# Sheet2.net
KiCad netlist of a schematic drawn in Altium Designer
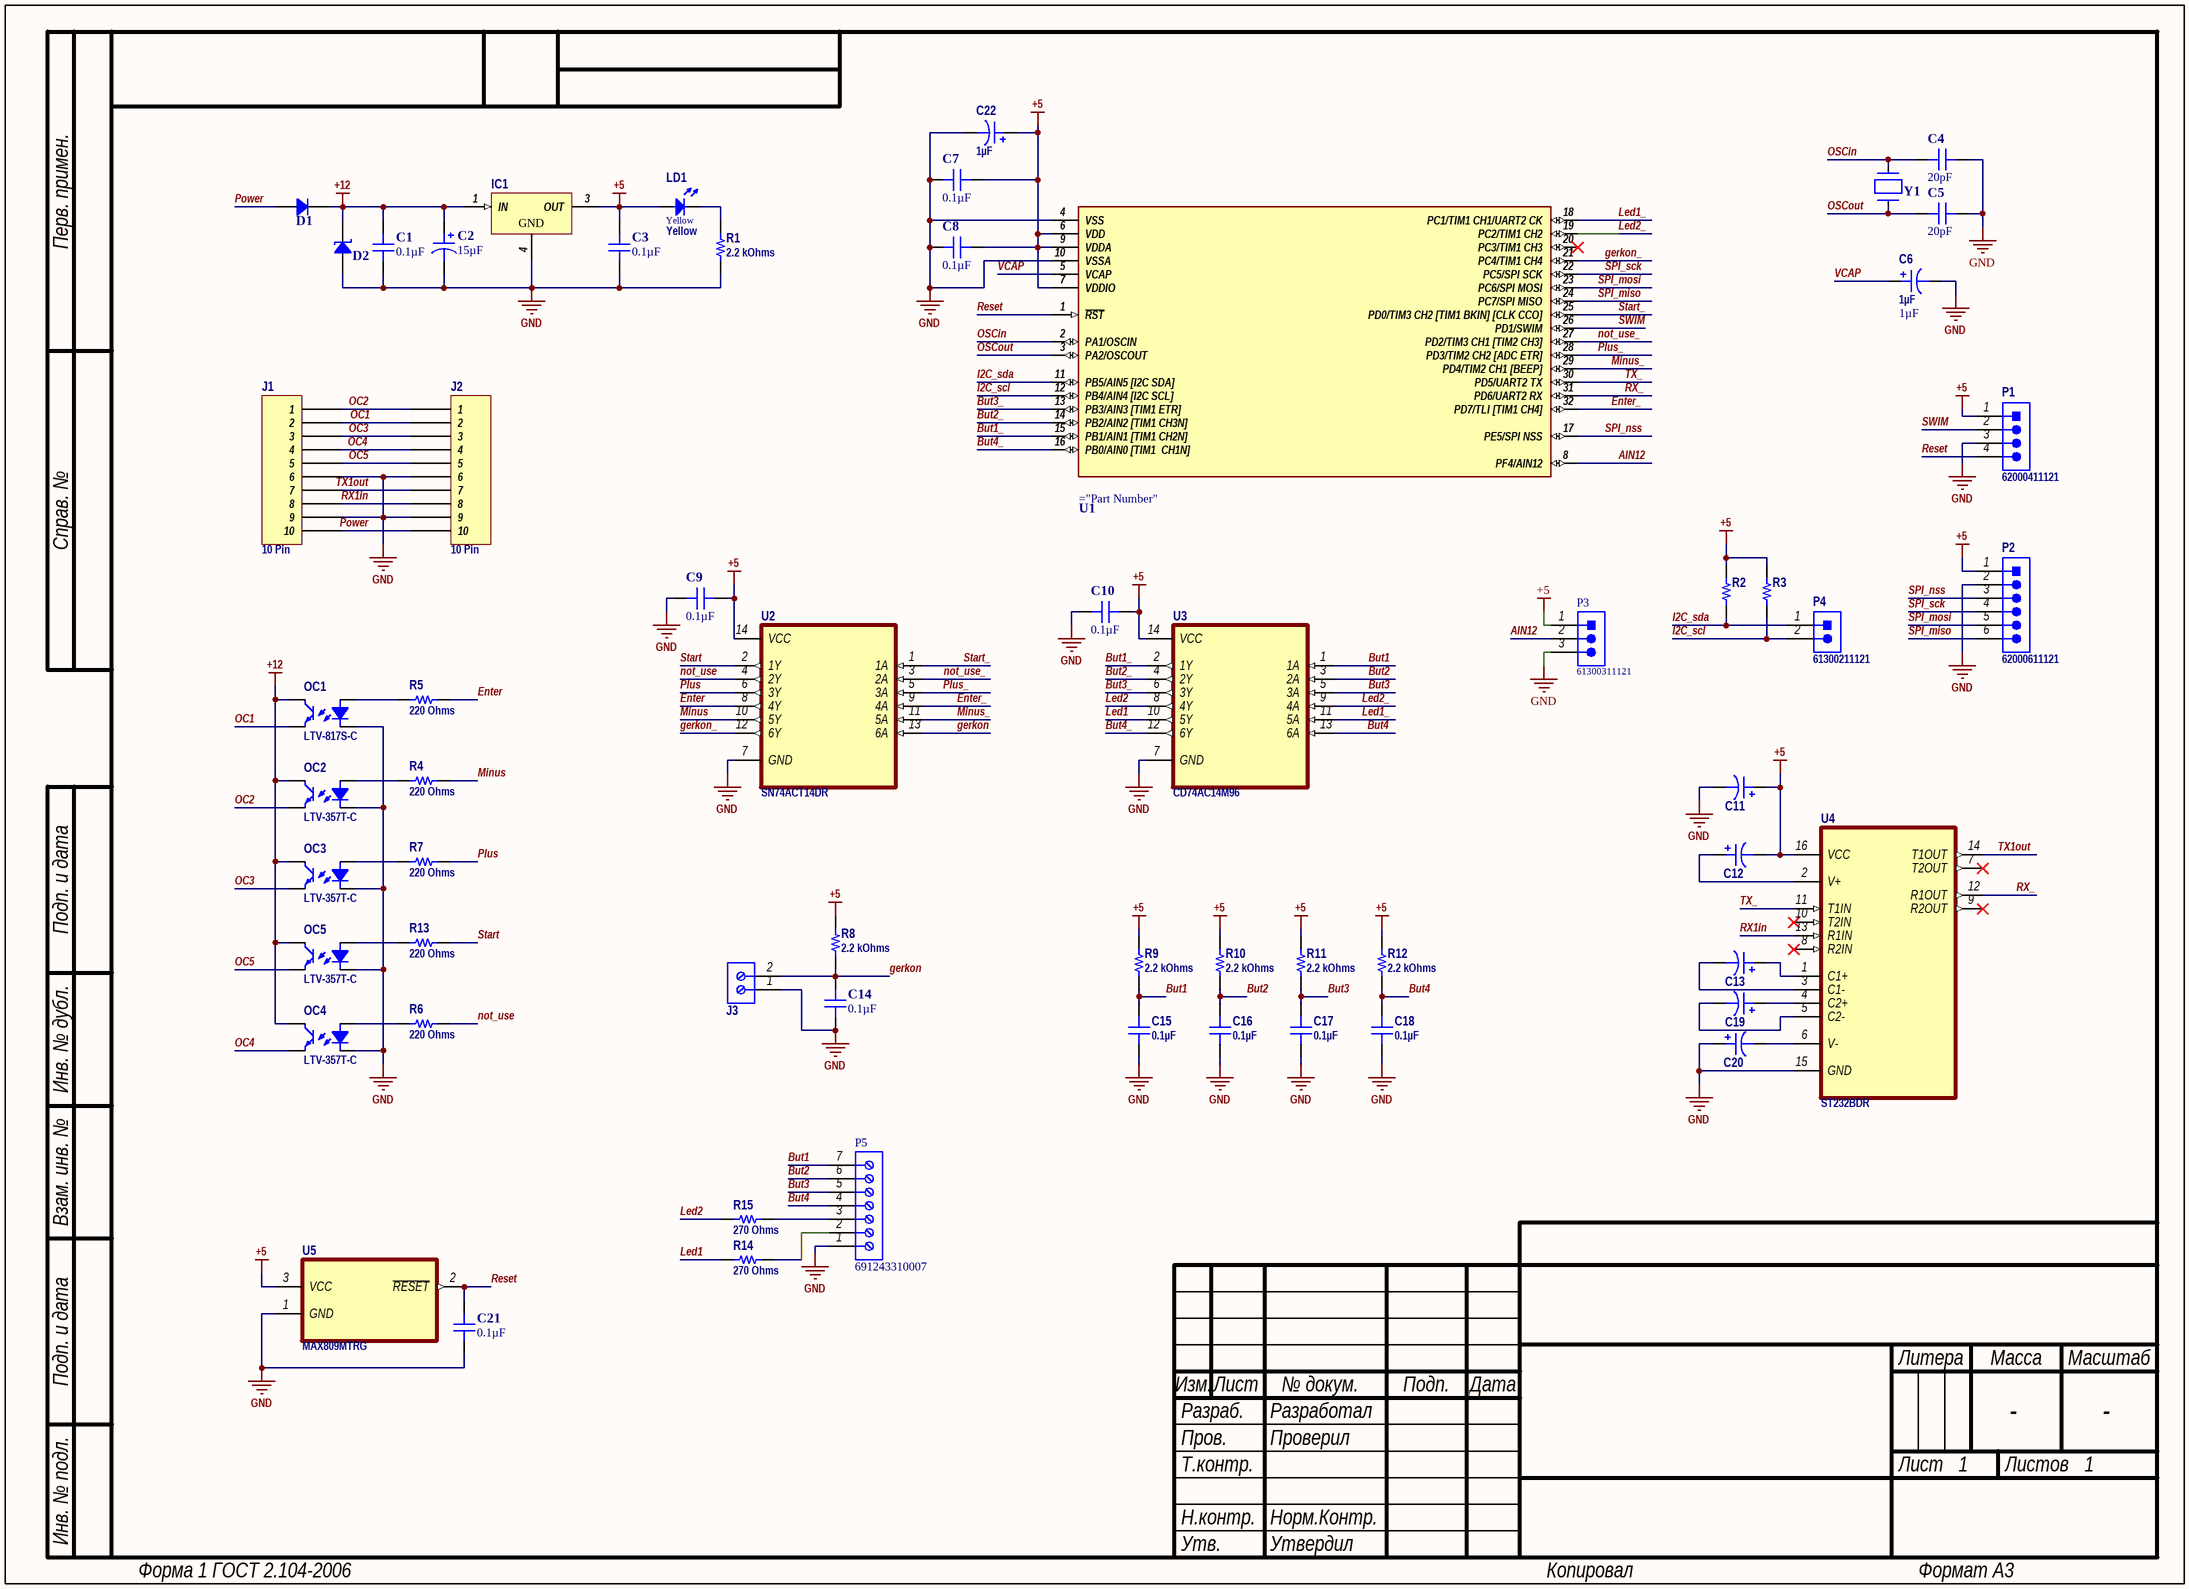
[diagram p0: Sheet2.SchDoc]

(export (version "E")
  (design (tool "Eeschema 10.0.6"))
  (components
    (comp (ref "C1")
      (value "0.1µF")
      (footprint "CAP 0603_1608")
      (description "CAP CER 0.1UF 50V X5R 0603")
      (fields (field (name "PART NUMBER") "CC0603KRX5R9BB104") (field (name "MANUFACTURER") "Yageo"))
      (libsource (lib "Celestial Altium Library - altium_library") (part "Capacitor"))
    )
    (comp (ref "C2")
      (value "15µF")
      (footprint "CAP POL 2917_7343")
      (description "CAP TANT 15UF 10% 35V 2917")
      (fields (field (name "PART NUMBER") "593D156X9035D2TE3") (field (name "MANUFACTURER") "Vishay Sprague"))
      (libsource (lib "") (part "Polarised Capacitor_1"))
    )
    (comp (ref "C3")
      (value "0.1µF")
      (footprint "CAP 0603_1608")
      (description "CAP CER 0.1UF 50V X5R 0603")
      (fields (field (name "PART NUMBER") "CC0603KRX5R9BB104") (field (name "MANUFACTURER") "Yageo"))
      (libsource (lib "Celestial Altium Library - altium_library") (part "Capacitor"))
    )
    (comp (ref "C4")
      (value "20pF")
      (footprint "CAP 0603_1608")
      (description "CAP CER 20PF 50V C0G/NPO 0603")
      (fields (field (name "PART NUMBER") "CC0603JRNPO9BN200") (field (name "MANUFACTURER") "Yageo"))
      (libsource (lib "Celestial Altium Library - altium_library") (part "Capacitor"))
    )
    (comp (ref "C5")
      (value "20pF")
      (footprint "CAP 0603_1608")
      (description "CAP CER 20PF 50V C0G/NPO 0603")
      (fields (field (name "PART NUMBER") "CC0603JRNPO9BN200") (field (name "MANUFACTURER") "Yageo"))
      (libsource (lib "Celestial Altium Library - altium_library") (part "Capacitor"))
    )
    (comp (ref "C6")
      (value "1µF")
      (footprint "CAP POL 1206_3216")
      (description "CAP TANT 1UF 10% 20V 1206")
      (fields
        (field (name "PART NUMBER") "293D105X9020A2TE3")
        (field (name "ALTIUM_VALUE") "1µF")
        (field (name "MANUFACTURER") "Vishay Sprague")
      )
      (libsource (lib "Celestial Altium Library - altium_library") (part "Polarised Capacitor"))
    )
    (comp (ref "C7")
      (value "0.1µF")
      (footprint "CAP 0603_1608")
      (description "CAP CER 0.1UF 50V X5R 0603")
      (fields (field (name "PART NUMBER") "CC0603KRX5R9BB104") (field (name "MANUFACTURER") "Yageo"))
      (libsource (lib "Celestial Altium Library - altium_library") (part "Capacitor"))
    )
    (comp (ref "C8")
      (value "0.1µF")
      (footprint "CAP 0603_1608")
      (description "CAP CER 0.1UF 50V X5R 0603")
      (fields (field (name "PART NUMBER") "CC0603KRX5R9BB104") (field (name "MANUFACTURER") "Yageo"))
      (libsource (lib "Celestial Altium Library - altium_library") (part "Capacitor"))
    )
    (comp (ref "C9")
      (value "0.1µF")
      (footprint "CAP 0603_1608")
      (description "CAP CER 0.1UF 50V X5R 0603")
      (fields (field (name "PART NUMBER") "CC0603KRX5R9BB104") (field (name "MANUFACTURER") "Yageo"))
      (libsource (lib "Celestial Altium Library - altium_library") (part "Capacitor"))
    )
    (comp (ref "C10")
      (value "0.1µF")
      (footprint "CAP 0603_1608")
      (description "CAP CER 0.1UF 50V X5R 0603")
      (fields (field (name "PART NUMBER") "CC0603KRX5R9BB104") (field (name "MANUFACTURER") "Yageo"))
      (libsource (lib "Celestial Altium Library - altium_library") (part "Capacitor"))
    )
    (comp (ref "C11")
      (value "0.47µF")
      (footprint "CAP POL 1206_3216")
      (description "CAP TANT 0.47UF 10% 35V 1206")
      (fields (field (name "PART NUMBER") "293D474X9035A2TE3") (field (name "MANUFACTURER") "Vishay Sprague"))
      (libsource (lib "Celestial Altium Library - altium_library") (part "Polarised Capacitor"))
    )
    (comp (ref "C12")
      (value "0.47µF")
      (footprint "CAP POL 1206_3216")
      (description "CAP TANT 0.47UF 10% 35V 1206")
      (fields (field (name "PART NUMBER") "293D474X9035A2TE3") (field (name "MANUFACTURER") "Vishay Sprague"))
      (libsource (lib "Celestial Altium Library - altium_library") (part "Polarised Capacitor"))
    )
    (comp (ref "C13")
      (value "0.47µF")
      (footprint "CAP POL 1206_3216")
      (description "CAP TANT 0.47UF 10% 35V 1206")
      (fields (field (name "PART NUMBER") "293D474X9035A2TE3") (field (name "MANUFACTURER") "Vishay Sprague"))
      (libsource (lib "Celestial Altium Library - altium_library") (part "Polarised Capacitor"))
    )
    (comp (ref "C14")
      (value "0.1µF")
      (footprint "CAP 0603_1608")
      (description "CAP CER 0.1UF 50V X5R 0603")
      (fields (field (name "PART NUMBER") "CC0603KRX5R9BB104") (field (name "MANUFACTURER") "Yageo"))
      (libsource (lib "Celestial Altium Library - altium_library") (part "Capacitor"))
    )
    (comp (ref "C15")
      (value "0.1µF")
      (footprint "CAP 0402_1005")
      (description "CAP CER 0.1UF 10V X5R 0402")
      (fields
        (field (name "PART NUMBER") "CGA2B2X5R1A104K050BA")
        (field (name "MANUFACTURER") "TDK Corporation")
      )
      (libsource (lib "Sitiboard_1") (part "CGA2B2X5R1A104K050BA"))
    )
    (comp (ref "C16")
      (value "0.1µF")
      (footprint "CAP 0402_1005")
      (description "CAP CER 0.1UF 10V X5R 0402")
      (fields
        (field (name "PART NUMBER") "CGA2B2X5R1A104K050BA")
        (field (name "MANUFACTURER") "TDK Corporation")
      )
      (libsource (lib "Sitiboard_1") (part "CGA2B2X5R1A104K050BA"))
    )
    (comp (ref "C17")
      (value "0.1µF")
      (footprint "CAP 0402_1005")
      (description "CAP CER 0.1UF 10V X5R 0402")
      (fields
        (field (name "PART NUMBER") "CGA2B2X5R1A104K050BA")
        (field (name "MANUFACTURER") "TDK Corporation")
      )
      (libsource (lib "Sitiboard_1") (part "CGA2B2X5R1A104K050BA"))
    )
    (comp (ref "C18")
      (value "0.1µF")
      (footprint "CAP 0402_1005")
      (description "CAP CER 0.1UF 10V X5R 0402")
      (fields
        (field (name "PART NUMBER") "CGA2B2X5R1A104K050BA")
        (field (name "MANUFACTURER") "TDK Corporation")
      )
      (libsource (lib "Sitiboard_1") (part "CGA2B2X5R1A104K050BA"))
    )
    (comp (ref "C19")
      (value "0.47µF")
      (footprint "CAP POL 1206_3216")
      (description "CAP TANT 0.47UF 10% 35V 1206")
      (fields (field (name "PART NUMBER") "293D474X9035A2TE3") (field (name "MANUFACTURER") "Vishay Sprague"))
      (libsource (lib "Celestial Altium Library - altium_library") (part "Polarised Capacitor"))
    )
    (comp (ref "C20")
      (value "0.47µF")
      (footprint "CAP POL 1206_3216")
      (description "CAP TANT 0.47UF 10% 35V 1206")
      (fields (field (name "PART NUMBER") "293D474X9035A2TE3") (field (name "MANUFACTURER") "Vishay Sprague"))
      (libsource (lib "Celestial Altium Library - altium_library") (part "Polarised Capacitor"))
    )
    (comp (ref "C21")
      (value "0.1µF")
      (footprint "CAP 0603_1608")
      (description "CAP CER 0.1UF 50V X5R 0603")
      (fields (field (name "PART NUMBER") "CC0603KRX5R9BB104") (field (name "MANUFACTURER") "Yageo"))
      (libsource (lib "Celestial Altium Library - altium_library") (part "Capacitor"))
    )
    (comp (ref "C22")
      (value "1µF")
      (footprint "CAP POL 1206_3216")
      (description "CAP TANT 1UF 10% 20V 1206")
      (fields (field (name "PART NUMBER") "293D105X9020A2TE3") (field (name "MANUFACTURER") "Vishay Sprague"))
      (libsource (lib "Celestial Altium Library - altium_library") (part "Polarised Capacitor"))
    )
    (comp (ref "D1")
      (value "SS24FL")
      (footprint "SOD-123W")
      (description "Rectifier Diode")
      (libsource (lib "Sitiboard_1") (part "Diode"))
    )
    (comp (ref "D2")
      (value "SMBJ15CA-E3/52")
      (footprint "DO214AA SMB")
      (description "Rectifier Diode")
      (libsource (lib "Sitiboard_1") (part "DIODE TVS UNI"))
    )
    (comp (ref "IC1")
      (value "MC7805BDTG")
      (footprint "TO-252AA")
      (description "3-Terminal Regulator 1=IN 2=GND 3=OUT")
      (libsource (lib "Sitiboard_1") (part "REG3 1IN-2GND-3OUT"))
    )
    (comp (ref "J1")
      (value "10 Pin")
      (footprint "CON: IDC-10MS - 1_7mm")
      (libsource (lib "Sitiboard_1") (part "10 Pin"))
    )
    (comp (ref "J2")
      (value "10 Pin")
      (footprint "CON: IDC-10MS - 1_7mm")
      (libsource (lib "") (part "10 Pin_1"))
    )
    (comp (ref "J3")
      (value "691103110002")
      (footprint "691103110002")
      (description "WR-TBL Serie 1031 Horizontal Entry Modular, Pressure Clamp, THT, pitch 3.5mm, 2p")
      (fields (field (name "MANUFACTURER") "Wurth Elektronik"))
      (libsource (lib "Sitiboard_1") (part "691103110002"))
    )
    (comp (ref "LD1")
      (value "Yellow")
      (footprint "LED_KINGBRIGHT_KPH-1608YC")
      (description "LED Yellow 1C 2A")
      (fields
        (field (name "PART NUMBER") "LED_KINGBRIGHT_KPH-1608YC")
        (field (name "MANUFACTURER") "KINGBRIGHT")
        (field (name "AUTHOR") "CERN DEM JLC")
      )
      (libsource (lib "Sitiboard_1") (part "LED_KINGBRIGHT_KPH-1608YC"))
    )
    (comp (ref "OC1")
      (value "LTV-817S-C")
      (footprint "LITEON LTV-817")
      (libsource (lib "Sitiboard_1") (part "Optoisolator"))
    )
    (comp (ref "OC2")
      (value "LTV-357T-C")
      (footprint "LITEON LTV-357T")
      (libsource (lib "Sitiboard_1") (part "Optoisolator_1"))
    )
    (comp (ref "OC3")
      (value "LTV-357T-C")
      (footprint "LITEON LTV-357T")
      (libsource (lib "Sitiboard_1") (part "Optoisolator_1"))
    )
    (comp (ref "OC4")
      (value "LTV-357T-C")
      (footprint "LITEON LTV-357T")
      (libsource (lib "Sitiboard_1") (part "Optoisolator_1"))
    )
    (comp (ref "OC5")
      (value "LTV-357T-C")
      (footprint "LITEON LTV-357T")
      (libsource (lib "Sitiboard_1") (part "Optoisolator_1"))
    )
    (comp (ref "P1")
      (value "62000411121")
      (footprint "62000411121")
      (description "WR-PHD Pin Header, THT, pitch 2mm, Single Row, Vertical, 4p")
      (fields (field (name "MANUFACTURER") "Wurth Elektronik"))
      (libsource (lib "Altium_WR-PHD (rev22a)") (part "62000411121"))
    )
    (comp (ref "P2")
      (value "62000611121")
      (footprint "62000611121")
      (description "WR-PHD Pin Header, THT, pitch 2mm, Single Row, Vertical, 6p")
      (fields (field (name "MANUFACTURER") "Wurth Elektronik"))
      (libsource (lib "Altium_WR-PHD (rev22a)") (part "62000611121"))
    )
    (comp (ref "P3")
      (value "61300311121")
      (footprint "61300311121")
      (description "WR-PHD Pin Header, THT, pitch 2.54mm, Single Row, Vertical, 3p")
      (fields (field (name "MANUFACTURER") "Wurth Elektronik"))
      (libsource (lib "Altium_WR-PHD (rev22a)") (part "61300311121"))
    )
    (comp (ref "P4")
      (value "61300211121")
      (footprint "61300211121")
      (description "WR-PHD Pin Header, THT, pitch 2.54mm, Single Row, Vertical, 2p")
      (fields (field (name "MANUFACTURER") "Wurth Elektronik"))
      (libsource (lib "Altium_WR-PHD (rev22a)") (part "61300211121"))
    )
    (comp (ref "P5")
      (value "691243310007")
      (footprint "691243310007")
      (description "WR-TBL Serie 2433 Horizontal Entry Modular, Rising Cage Clamp, THT, pitch 3.81mm, 7p")
      (fields (field (name "MANUFACTURER") "Wurth Elektronik"))
      (libsource (lib "Altium_WR-TBL (rev21a)") (part "691243310007"))
    )
    (comp (ref "R1")
      (value "2.2 kOhms")
      (footprint "RES 0603_1608")
      (description "RES SMD 2.2K OHM 5% 1/10W 0603")
      (fields (field (name "PART NUMBER") "RC0603JR-072K2L") (field (name "MANUFACTURER") "Yageo"))
      (libsource (lib "Sitiboard_1") (part "RC0603JR-072K2L"))
    )
    (comp (ref "R2")
      (value "2.2 kOhms")
      (footprint "RES 0603_1608")
      (description "RES SMD 2.2K OHM 5% 1/10W 0603")
      (fields (field (name "PART NUMBER") "RC0603JR-072K2L") (field (name "MANUFACTURER") "Yageo"))
      (libsource (lib "Sitiboard_1") (part "RC0603JR-072K2L"))
    )
    (comp (ref "R3")
      (value "2.2 kOhms")
      (footprint "RES 0603_1608")
      (description "RES SMD 2.2K OHM 5% 1/10W 0603")
      (fields (field (name "PART NUMBER") "RC0603JR-072K2L") (field (name "MANUFACTURER") "Yageo"))
      (libsource (lib "Sitiboard_1") (part "RC0603JR-072K2L"))
    )
    (comp (ref "R4")
      (value "220 Ohms")
      (footprint "RES 0603_1608")
      (description "RES SMD 220 OHM 5% 1/10W 0603")
      (fields (field (name "PART NUMBER") "AC0603JR-07220RL") (field (name "MANUFACTURER") "Yageo"))
      (libsource (lib "Sitiboard_1") (part "AC0603JR-07220RL"))
    )
    (comp (ref "R5")
      (value "220 Ohms")
      (footprint "RES 0603_1608")
      (description "RES SMD 220 OHM 5% 1/10W 0603")
      (fields (field (name "PART NUMBER") "AC0603JR-07220RL") (field (name "MANUFACTURER") "Yageo"))
      (libsource (lib "Sitiboard_1") (part "AC0603JR-07220RL"))
    )
    (comp (ref "R6")
      (value "220 Ohms")
      (footprint "RES 0603_1608")
      (description "RES SMD 220 OHM 5% 1/10W 0603")
      (fields (field (name "PART NUMBER") "AC0603JR-07220RL") (field (name "MANUFACTURER") "Yageo"))
      (libsource (lib "Sitiboard_1") (part "AC0603JR-07220RL"))
    )
    (comp (ref "R7")
      (value "220 Ohms")
      (footprint "RES 0603_1608")
      (description "RES SMD 220 OHM 5% 1/10W 0603")
      (fields (field (name "PART NUMBER") "AC0603JR-07220RL") (field (name "MANUFACTURER") "Yageo"))
      (libsource (lib "Sitiboard_1") (part "AC0603JR-07220RL"))
    )
    (comp (ref "R8")
      (value "2.2 kOhms")
      (footprint "RES 0603_1608")
      (description "RES SMD 2.2K OHM 5% 1/10W 0603")
      (fields (field (name "PART NUMBER") "RC0603JR-072K2L") (field (name "MANUFACTURER") "Yageo"))
      (libsource (lib "Sitiboard_1") (part "RC0603JR-072K2L"))
    )
    (comp (ref "R9")
      (value "2.2 kOhms")
      (footprint "RES 0603_1608")
      (description "RES SMD 2.2K OHM 5% 1/10W 0603")
      (fields (field (name "PART NUMBER") "RC0603JR-072K2L") (field (name "MANUFACTURER") "Yageo"))
      (libsource (lib "Sitiboard_1") (part "RC0603JR-072K2L"))
    )
    (comp (ref "R10")
      (value "2.2 kOhms")
      (footprint "RES 0603_1608")
      (description "RES SMD 2.2K OHM 5% 1/10W 0603")
      (fields (field (name "PART NUMBER") "RC0603JR-072K2L") (field (name "MANUFACTURER") "Yageo"))
      (libsource (lib "Sitiboard_1") (part "RC0603JR-072K2L"))
    )
    (comp (ref "R11")
      (value "2.2 kOhms")
      (footprint "RES 0603_1608")
      (description "RES SMD 2.2K OHM 5% 1/10W 0603")
      (fields (field (name "PART NUMBER") "RC0603JR-072K2L") (field (name "MANUFACTURER") "Yageo"))
      (libsource (lib "Sitiboard_1") (part "RC0603JR-072K2L"))
    )
    (comp (ref "R12")
      (value "2.2 kOhms")
      (footprint "RES 0603_1608")
      (description "RES SMD 2.2K OHM 5% 1/10W 0603")
      (fields (field (name "PART NUMBER") "RC0603JR-072K2L") (field (name "MANUFACTURER") "Yageo"))
      (libsource (lib "Sitiboard_1") (part "RC0603JR-072K2L"))
    )
    (comp (ref "R13")
      (value "220 Ohms")
      (footprint "RES 0603_1608")
      (description "RES SMD 220 OHM 5% 1/10W 0603")
      (fields (field (name "PART NUMBER") "AC0603JR-07220RL") (field (name "MANUFACTURER") "Yageo"))
      (libsource (lib "Sitiboard_1") (part "AC0603JR-07220RL"))
    )
    (comp (ref "R14")
      (value "270 Ohms")
      (footprint "RES 0805_2012")
      (description "RES SMD 270 OHM 5% 1/8W 0805")
      (fields (field (name "PART NUMBER") "RC0805JR-07270RL") (field (name "MANUFACTURER") "Yageo"))
      (libsource (lib "Sitiboard_1") (part "RC0805JR-07270RL"))
    )
    (comp (ref "R15")
      (value "270 Ohms")
      (footprint "RES 0805_2012")
      (description "RES SMD 270 OHM 5% 1/8W 0805")
      (fields (field (name "PART NUMBER") "RC0805JR-07270RL") (field (name "MANUFACTURER") "Yageo"))
      (libsource (lib "Sitiboard_1") (part "RC0805JR-07270RL"))
    )
    (comp (ref "U1")
      (value "STM8S005K6T6C")
      (footprint "STMicroelectronics_LQFP32-5V_0")
      (libsource (lib "IC_STMicroelectronics_STM8S005K6T6C_eec") (part "STM8S005K6T6C"))
    )
    (comp (ref "U2")
      (value "SN74ACT14DR")
      (footprint "14-SOIC")
      (libsource (lib "Sitiboard_1") (part "SN74ACT14DR"))
    )
    (comp (ref "U3")
      (value "CD74AC14M96")
      (footprint "SOIC127P600X175-14N")
      (description "Hex Schmitt-Triggered Inverters 14-SOIC -55 to 125")
      (fields (field (name "MF") "Texas Instruments"))
      (libsource (lib "CD74AC14M96") (part "CD74AC14M96"))
    )
    (comp (ref "U4")
      (value "ST232BDR")
      (footprint "16-SO")
      (description "2/2 Transceiver Full RS232 16-SO")
      (fields (field (name "MF") "STMicroelectronics"))
      (libsource (lib "Sitiboard_1") (part "ST232BDR"))
    )
    (comp (ref "U5")
      (value "MAX809MTRG")
      (footprint "SOT95P240X111-3N")
      (description "Supervisor Push-Pull, Totem Pole 1 Channel SOT-23-3 (TO-236)")
      (fields (field (name "MF") "ON Semiconductor") (field (name "MP") "MAX809TTRG"))
      (libsource (lib "Sitiboard_1") (part "MAX809TTRG"))
    )
    (comp (ref "Y1")
      (value "Crys_Abracon_ABL-16.000MHZ-B2_eec")
      (footprint "Abracon_ABL-16.000MHZ-B2_0")
      (description "CRYS 16MHz ±20ppm Crystal 18pF 40 Ohm -20°C ~ 70°C Through Hole HC49/US")
      (fields (field (name "PART NUMBER") "ABL-16.000MHZ-B2") (field (name "MANUFACTURER") "Abracon"))
      (libsource (lib "Crys_Abracon_ABL-16.000MHZ-B2_eec") (part "Crys_Abracon_ABL-16.000MHZ-B2_eec"))
    )
  )
  (nets
    (net (code "1") (name "+5") (class "Default")
      (node (ref "C10") (pin "1") (pinfunction "1_1") (pintype "passive"))
      (node (ref "C11") (pin "1") (pinfunction "1_1") (pintype "passive"))
      (node (ref "C12") (pin "2") (pinfunction "2_2") (pintype "passive"))
      (node (ref "C22") (pin "1") (pinfunction "1_1") (pintype "passive"))
      (node (ref "C3") (pin "2") (pinfunction "2_2") (pintype "passive"))
      (node (ref "C7") (pin "2") (pinfunction "2_2") (pintype "passive"))
      (node (ref "C8") (pin "1") (pinfunction "1_1") (pintype "passive"))
      (node (ref "C9") (pin "1") (pinfunction "1_1") (pintype "passive"))
      (node (ref "IC1") (pin "3") (pinfunction "OUT_3") (pintype "power_in"))
      (node (ref "LD1") (pin "2") (pinfunction "A_2") (pintype "passive"))
      (node (ref "P1") (pin "1") (pinfunction "1_1") (pintype "passive"))
      (node (ref "P2") (pin "1") (pinfunction "1_1") (pintype "passive"))
      (node (ref "P3") (pin "1") (pinfunction "1_1") (pintype "passive"))
      (node (ref "R10") (pin "2") (pinfunction "2_2") (pintype "passive"))
      (node (ref "R11") (pin "2") (pinfunction "2_2") (pintype "passive"))
      (node (ref "R12") (pin "2") (pinfunction "2_2") (pintype "passive"))
      (node (ref "R2") (pin "2") (pinfunction "2_2") (pintype "passive"))
      (node (ref "R3") (pin "2") (pinfunction "2_2") (pintype "passive"))
      (node (ref "R8") (pin "2") (pinfunction "2_2") (pintype "passive"))
      (node (ref "R9") (pin "2") (pinfunction "2_2") (pintype "passive"))
      (node (ref "U1") (pin "6") (pinfunction "VDD_6") (pintype "power_in"))
      (node (ref "U1") (pin "7") (pinfunction "VDDIO_7") (pintype "power_in"))
      (node (ref "U1") (pin "9") (pinfunction "VDDA_9") (pintype "power_in"))
      (node (ref "U2") (pin "14") (pinfunction "VCC_14") (pintype "power_in"))
      (node (ref "U3") (pin "14") (pinfunction "VCC_14") (pintype "power_in"))
      (node (ref "U4") (pin "16") (pinfunction "VCC_16") (pintype "power_in"))
      (node (ref "U5") (pin "3") (pinfunction "VCC_3") (pintype "power_in"))
    )
    (net (code "2") (name "+12") (class "Default")
      (node (ref "C1") (pin "2") (pinfunction "2_2") (pintype "passive"))
      (node (ref "C2") (pin "1") (pinfunction "1_1") (pintype "passive"))
      (node (ref "D1") (pin "2") (pinfunction "2_2") (pintype "passive"))
      (node (ref "D2") (pin "2") (pinfunction "2_2") (pintype "passive"))
      (node (ref "IC1") (pin "1") (pinfunction "IN_1") (pintype "input"))
      (node (ref "OC1") (pin "4") (pinfunction "4_4") (pintype "passive"))
      (node (ref "OC2") (pin "4") (pinfunction "4_4") (pintype "passive"))
      (node (ref "OC3") (pin "4") (pinfunction "4_4") (pintype "passive"))
      (node (ref "OC4") (pin "4") (pinfunction "4_4") (pintype "passive"))
      (node (ref "OC5") (pin "4") (pinfunction "4_4") (pintype "passive"))
    )
    (net (code "3") (name "/AIN12") (class "Default")
      (node (ref "P3") (pin "2") (pinfunction "2_2") (pintype "passive"))
      (node (ref "U1") (pin "8") (pinfunction "PF4/AIN12_8") (pintype "bidirectional"))
    )
    (net (code "4") (name "/But1") (class "Default")
      (node (ref "C15") (pin "2") (pinfunction "2_2") (pintype "passive"))
      (node (ref "P5") (pin "7") (pinfunction "7_7") (pintype "passive"))
      (node (ref "R9") (pin "1") (pinfunction "1_1") (pintype "passive"))
      (node (ref "U3") (pin "1") (pinfunction "1A_1") (pintype "input"))
    )
    (net (code "5") (name "/But1_") (class "Default")
      (node (ref "U1") (pin "15") (pinfunction "PB1/AIN1_[TIM1_CH2N]_15") (pintype "bidirectional"))
      (node (ref "U3") (pin "2") (pinfunction "1Y_2") (pintype "output"))
    )
    (net (code "6") (name "/But2") (class "Default")
      (node (ref "C16") (pin "2") (pinfunction "2_2") (pintype "passive"))
      (node (ref "P5") (pin "6") (pinfunction "6_6") (pintype "passive"))
      (node (ref "R10") (pin "1") (pinfunction "1_1") (pintype "passive"))
      (node (ref "U3") (pin "3") (pinfunction "2A_3") (pintype "input"))
    )
    (net (code "7") (name "/But2_") (class "Default")
      (node (ref "U1") (pin "14") (pinfunction "PB2/AIN2_[TIM1_CH3N]_14") (pintype "bidirectional"))
      (node (ref "U3") (pin "4") (pinfunction "2Y_4") (pintype "output"))
    )
    (net (code "8") (name "/But3") (class "Default")
      (node (ref "C17") (pin "2") (pinfunction "2_2") (pintype "passive"))
      (node (ref "P5") (pin "5") (pinfunction "5_5") (pintype "passive"))
      (node (ref "R11") (pin "1") (pinfunction "1_1") (pintype "passive"))
      (node (ref "U3") (pin "5") (pinfunction "3A_5") (pintype "input"))
    )
    (net (code "9") (name "/But3_") (class "Default")
      (node (ref "U1") (pin "13") (pinfunction "PB3/AIN3_[TIM1_ETR]_13") (pintype "bidirectional"))
      (node (ref "U3") (pin "6") (pinfunction "3Y_6") (pintype "output"))
    )
    (net (code "10") (name "/But4") (class "Default")
      (node (ref "C18") (pin "2") (pinfunction "2_2") (pintype "passive"))
      (node (ref "P5") (pin "4") (pinfunction "4_4") (pintype "passive"))
      (node (ref "R12") (pin "1") (pinfunction "1_1") (pintype "passive"))
      (node (ref "U3") (pin "13") (pinfunction "6A_13") (pintype "input"))
    )
    (net (code "11") (name "/But4_") (class "Default")
      (node (ref "U1") (pin "16") (pinfunction "PB0/AIN0_[TIM1__CH1N]_16") (pintype "bidirectional"))
      (node (ref "U3") (pin "12") (pinfunction "6Y_12") (pintype "output"))
    )
    (net (code "12") (name "/Enter") (class "Default")
      (node (ref "R5") (pin "2") (pinfunction "2_2") (pintype "passive"))
      (node (ref "U2") (pin "8") (pinfunction "4Y_8") (pintype "output"))
    )
    (net (code "13") (name "/Enter_") (class "Default")
      (node (ref "U1") (pin "32") (pinfunction "PD7/TLI_[TIM1_CH4]_32") (pintype "bidirectional"))
      (node (ref "U2") (pin "9") (pinfunction "4A_9") (pintype "input"))
    )
    (net (code "14") (name "/I2C_scl") (class "Default")
      (node (ref "P4") (pin "2") (pinfunction "2_2") (pintype "passive"))
      (node (ref "R3") (pin "1") (pinfunction "1_1") (pintype "passive"))
      (node (ref "U1") (pin "12") (pinfunction "PB4/AIN4_[I2C_SCL]_12") (pintype "bidirectional"))
    )
    (net (code "15") (name "/I2C_sda") (class "Default")
      (node (ref "P4") (pin "1") (pinfunction "1_1") (pintype "passive"))
      (node (ref "R2") (pin "1") (pinfunction "1_1") (pintype "passive"))
      (node (ref "U1") (pin "11") (pinfunction "PB5/AIN5_[I2C_SDA]_11") (pintype "bidirectional"))
    )
    (net (code "16") (name "/Led1") (class "Default")
      (node (ref "R14") (pin "1") (pinfunction "1_1") (pintype "passive"))
      (node (ref "U3") (pin "10") (pinfunction "5Y_10") (pintype "output"))
    )
    (net (code "17") (name "/Led1_") (class "Default")
      (node (ref "U1") (pin "18") (pinfunction "PC1/TIM1_CH1/UART2_CK_18") (pintype "bidirectional"))
      (node (ref "U3") (pin "11") (pinfunction "5A_11") (pintype "input"))
    )
    (net (code "18") (name "/Led2") (class "Default")
      (node (ref "R15") (pin "1") (pinfunction "1_1") (pintype "passive"))
      (node (ref "U3") (pin "8") (pinfunction "4Y_8") (pintype "output"))
    )
    (net (code "19") (name "/Led2_") (class "Default")
      (node (ref "U1") (pin "19") (pinfunction "PC2/TIM1_CH2_19") (pintype "bidirectional"))
      (node (ref "U3") (pin "9") (pinfunction "4A_9") (pintype "input"))
    )
    (net (code "20") (name "/Minus") (class "Default")
      (node (ref "R4") (pin "2") (pinfunction "2_2") (pintype "passive"))
      (node (ref "U2") (pin "10") (pinfunction "5Y_10") (pintype "output"))
    )
    (net (code "21") (name "/Minus_") (class "Default")
      (node (ref "U1") (pin "29") (pinfunction "PD4/TIM2_CH1_[BEEP]_29") (pintype "bidirectional"))
      (node (ref "U2") (pin "11") (pinfunction "5A_11") (pintype "input"))
    )
    (net (code "22") (name "/OC1") (class "Default")
      (node (ref "J1") (pin "2") (pinfunction "2_2") (pintype "passive"))
      (node (ref "J2") (pin "2") (pinfunction "2_2") (pintype "passive"))
      (node (ref "OC1") (pin "3") (pinfunction "3_3") (pintype "passive"))
    )
    (net (code "23") (name "/OC2") (class "Default")
      (node (ref "J1") (pin "1") (pinfunction "1_1") (pintype "passive"))
      (node (ref "J2") (pin "1") (pinfunction "1_1") (pintype "passive"))
      (node (ref "OC2") (pin "3") (pinfunction "3_3") (pintype "passive"))
    )
    (net (code "24") (name "/OC3") (class "Default")
      (node (ref "J1") (pin "3") (pinfunction "3_3") (pintype "passive"))
      (node (ref "J2") (pin "3") (pinfunction "3_3") (pintype "passive"))
      (node (ref "OC3") (pin "3") (pinfunction "3_3") (pintype "passive"))
    )
    (net (code "25") (name "/OC4") (class "Default")
      (node (ref "J1") (pin "4") (pinfunction "4_4") (pintype "passive"))
      (node (ref "J2") (pin "4") (pinfunction "4_4") (pintype "passive"))
      (node (ref "OC4") (pin "3") (pinfunction "3_3") (pintype "passive"))
    )
    (net (code "26") (name "/OC5") (class "Default")
      (node (ref "J1") (pin "5") (pinfunction "5_5") (pintype "passive"))
      (node (ref "J2") (pin "5") (pinfunction "5_5") (pintype "passive"))
      (node (ref "OC5") (pin "3") (pinfunction "3_3") (pintype "passive"))
    )
    (net (code "27") (name "/OSCin") (class "Default")
      (node (ref "C4") (pin "2") (pinfunction "2_2") (pintype "passive"))
      (node (ref "U1") (pin "2") (pinfunction "PA1/OSCIN_2") (pintype "bidirectional"))
      (node (ref "Y1") (pin "1") (pinfunction "1_1") (pintype "passive"))
    )
    (net (code "28") (name "/OSCout") (class "Default")
      (node (ref "C5") (pin "2") (pinfunction "2_2") (pintype "passive"))
      (node (ref "U1") (pin "3") (pinfunction "PA2/OSCOUT_3") (pintype "bidirectional"))
      (node (ref "Y1") (pin "2") (pinfunction "2_2") (pintype "passive"))
    )
    (net (code "29") (name "/Plus") (class "Default")
      (node (ref "R7") (pin "2") (pinfunction "2_2") (pintype "passive"))
      (node (ref "U2") (pin "6") (pinfunction "3Y_6") (pintype "output"))
    )
    (net (code "30") (name "/Plus_") (class "Default")
      (node (ref "U1") (pin "28") (pinfunction "PD3/TIM2_CH2_[ADC_ETR]_28") (pintype "bidirectional"))
      (node (ref "U2") (pin "5") (pinfunction "3A_5") (pintype "input"))
    )
    (net (code "31") (name "/Power") (class "Default")
      (node (ref "D1") (pin "1") (pinfunction "1_1") (pintype "passive"))
      (node (ref "J1") (pin "10") (pinfunction "10_10") (pintype "passive"))
      (node (ref "J2") (pin "10") (pinfunction "10_10") (pintype "passive"))
    )
    (net (code "32") (name "/RX1in") (class "Default")
      (node (ref "J1") (pin "8") (pinfunction "8_8") (pintype "passive"))
      (node (ref "J2") (pin "8") (pinfunction "8_8") (pintype "passive"))
      (node (ref "U4") (pin "13") (pinfunction "R1IN_13") (pintype "input"))
    )
    (net (code "33") (name "/RX_") (class "Default")
      (node (ref "U1") (pin "31") (pinfunction "PD6/UART2_RX_31") (pintype "bidirectional"))
      (node (ref "U4") (pin "12") (pinfunction "R1OUT_12") (pintype "output"))
    )
    (net (code "34") (name "/Reset") (class "Default")
      (node (ref "C21") (pin "2") (pinfunction "2_2") (pintype "passive"))
      (node (ref "P1") (pin "4") (pinfunction "4_4") (pintype "passive"))
      (node (ref "U1") (pin "1") (pinfunction "~{RST}_1") (pintype "input"))
      (node (ref "U5") (pin "2") (pinfunction "~{RESET}_2") (pintype "output"))
    )
    (net (code "35") (name "/SPI_miso") (class "Default")
      (node (ref "P2") (pin "6") (pinfunction "6_6") (pintype "passive"))
      (node (ref "U1") (pin "24") (pinfunction "PC7/SPI_MISO_24") (pintype "bidirectional"))
    )
    (net (code "36") (name "/SPI_mosi") (class "Default")
      (node (ref "P2") (pin "5") (pinfunction "5_5") (pintype "passive"))
      (node (ref "U1") (pin "23") (pinfunction "PC6/SPI_MOSI_23") (pintype "bidirectional"))
    )
    (net (code "37") (name "/SPI_nss") (class "Default")
      (node (ref "P2") (pin "3") (pinfunction "3_3") (pintype "passive"))
      (node (ref "U1") (pin "17") (pinfunction "PE5/SPI_NSS_17") (pintype "bidirectional"))
    )
    (net (code "38") (name "/SPI_sck") (class "Default")
      (node (ref "P2") (pin "4") (pinfunction "4_4") (pintype "passive"))
      (node (ref "U1") (pin "22") (pinfunction "PC5/SPI_SCK_22") (pintype "bidirectional"))
    )
    (net (code "39") (name "/SWIM") (class "Default")
      (node (ref "P1") (pin "2") (pinfunction "2_2") (pintype "passive"))
      (node (ref "U1") (pin "26") (pinfunction "PD1/SWIM_26") (pintype "bidirectional"))
    )
    (net (code "40") (name "/Start") (class "Default")
      (node (ref "R13") (pin "2") (pinfunction "2_2") (pintype "passive"))
      (node (ref "U2") (pin "2") (pinfunction "1Y_2") (pintype "output"))
    )
    (net (code "41") (name "/Start_") (class "Default")
      (node (ref "U1") (pin "25") (pinfunction "PD0/TIM3_CH2_[TIM1_BKIN]_[CLK_CCO]_25") (pintype "bidirectional"))
      (node (ref "U2") (pin "1") (pinfunction "1A_1") (pintype "input"))
    )
    (net (code "42") (name "/TX1out") (class "Default")
      (node (ref "J1") (pin "7") (pinfunction "7_7") (pintype "passive"))
      (node (ref "J2") (pin "7") (pinfunction "7_7") (pintype "passive"))
      (node (ref "U4") (pin "14") (pinfunction "T1OUT_14") (pintype "output"))
    )
    (net (code "43") (name "/TX_") (class "Default")
      (node (ref "U1") (pin "30") (pinfunction "PD5/UART2_TX_30") (pintype "bidirectional"))
      (node (ref "U4") (pin "11") (pinfunction "T1IN_11") (pintype "input"))
    )
    (net (code "44") (name "/VCAP") (class "Default")
      (node (ref "C6") (pin "1") (pinfunction "1_1") (pintype "passive"))
      (node (ref "U1") (pin "5") (pinfunction "VCAP_5") (pintype "power_in"))
    )
    (net (code "45") (name "/gerkon") (class "Default")
      (node (ref "C14") (pin "2") (pinfunction "2_2") (pintype "passive"))
      (node (ref "J3") (pin "2") (pinfunction "2_2") (pintype "passive"))
      (node (ref "R8") (pin "1") (pinfunction "1_1") (pintype "passive"))
      (node (ref "U2") (pin "13") (pinfunction "6A_13") (pintype "input"))
    )
    (net (code "46") (name "/gerkon_") (class "Default")
      (node (ref "U1") (pin "21") (pinfunction "PC4/TIM1_CH4_21") (pintype "bidirectional"))
      (node (ref "U2") (pin "12") (pinfunction "6Y_12") (pintype "output"))
    )
    (net (code "47") (name "/not_use") (class "Default")
      (node (ref "R6") (pin "2") (pinfunction "2_2") (pintype "passive"))
      (node (ref "U2") (pin "4") (pinfunction "2Y_4") (pintype "output"))
    )
    (net (code "48") (name "/not_use_") (class "Default")
      (node (ref "U1") (pin "27") (pinfunction "PD2/TIM3_CH1_[TIM2_CH3]_27") (pintype "bidirectional"))
      (node (ref "U2") (pin "3") (pinfunction "2A_3") (pintype "input"))
    )
    (net (code "49") (name "GND") (class "Default")
      (node (ref "C1") (pin "1") (pinfunction "1_1") (pintype "passive"))
      (node (ref "C10") (pin "2") (pinfunction "2_2") (pintype "passive"))
      (node (ref "C11") (pin "2") (pinfunction "2_2") (pintype "passive"))
      (node (ref "C14") (pin "1") (pinfunction "1_1") (pintype "passive"))
      (node (ref "C15") (pin "1") (pinfunction "1_1") (pintype "passive"))
      (node (ref "C16") (pin "1") (pinfunction "1_1") (pintype "passive"))
      (node (ref "C17") (pin "1") (pinfunction "1_1") (pintype "passive"))
      (node (ref "C18") (pin "1") (pinfunction "1_1") (pintype "passive"))
      (node (ref "C2") (pin "2") (pinfunction "2_2") (pintype "passive"))
      (node (ref "C20") (pin "1") (pinfunction "1_1") (pintype "passive"))
      (node (ref "C21") (pin "1") (pinfunction "1_1") (pintype "passive"))
      (node (ref "C22") (pin "2") (pinfunction "2_2") (pintype "passive"))
      (node (ref "C3") (pin "1") (pinfunction "1_1") (pintype "passive"))
      (node (ref "C4") (pin "1") (pinfunction "1_1") (pintype "passive"))
      (node (ref "C5") (pin "1") (pinfunction "1_1") (pintype "passive"))
      (node (ref "C6") (pin "2") (pinfunction "2_2") (pintype "passive"))
      (node (ref "C7") (pin "1") (pinfunction "1_1") (pintype "passive"))
      (node (ref "C8") (pin "2") (pinfunction "2_2") (pintype "passive"))
      (node (ref "C9") (pin "2") (pinfunction "2_2") (pintype "passive"))
      (node (ref "D2") (pin "1") (pinfunction "1_1") (pintype "passive"))
      (node (ref "IC1") (pin "4") (pinfunction "GND_4") (pintype "power_in"))
      (node (ref "J1") (pin "6") (pinfunction "6_6") (pintype "passive"))
      (node (ref "J1") (pin "9") (pinfunction "9_9") (pintype "passive"))
      (node (ref "J2") (pin "6") (pinfunction "6_6") (pintype "passive"))
      (node (ref "J2") (pin "9") (pinfunction "9_9") (pintype "passive"))
      (node (ref "J3") (pin "1") (pinfunction "1_1") (pintype "passive"))
      (node (ref "OC1") (pin "2") (pinfunction "2_2") (pintype "passive"))
      (node (ref "OC2") (pin "2") (pinfunction "2_2") (pintype "passive"))
      (node (ref "OC3") (pin "2") (pinfunction "2_2") (pintype "passive"))
      (node (ref "OC4") (pin "2") (pinfunction "2_2") (pintype "passive"))
      (node (ref "OC5") (pin "2") (pinfunction "2_2") (pintype "passive"))
      (node (ref "P1") (pin "3") (pinfunction "3_3") (pintype "passive"))
      (node (ref "P2") (pin "2") (pinfunction "2_2") (pintype "passive"))
      (node (ref "P3") (pin "3") (pinfunction "3_3") (pintype "passive"))
      (node (ref "P5") (pin "1") (pinfunction "1_1") (pintype "passive"))
      (node (ref "R1") (pin "1") (pinfunction "1_1") (pintype "passive"))
      (node (ref "U1") (pin "10") (pinfunction "VSSA_10") (pintype "power_in"))
      (node (ref "U1") (pin "4") (pinfunction "VSS_4") (pintype "power_in"))
      (node (ref "U2") (pin "7") (pinfunction "GND_7") (pintype "power_in"))
      (node (ref "U3") (pin "7") (pinfunction "GND_7") (pintype "power_in"))
      (node (ref "U4") (pin "15") (pinfunction "GND_15") (pintype "passive"))
      (node (ref "U5") (pin "1") (pinfunction "GND_1") (pintype "passive"))
    )
    (net (code "50") (name "Net-(LD1-C)") (class "Default")
      (node (ref "LD1") (pin "1") (pinfunction "C_1") (pintype "passive"))
      (node (ref "R1") (pin "2") (pinfunction "2_2") (pintype "passive"))
    )
    (net (code "51") (name "Net-(OC1-Pad1)") (class "Default")
      (node (ref "OC1") (pin "1") (pinfunction "1_1") (pintype "passive"))
      (node (ref "R5") (pin "1") (pinfunction "1_1") (pintype "passive"))
    )
    (net (code "52") (name "Net-(OC2-Pad1)") (class "Default")
      (node (ref "OC2") (pin "1") (pinfunction "1_1") (pintype "passive"))
      (node (ref "R4") (pin "1") (pinfunction "1_1") (pintype "passive"))
    )
    (net (code "53") (name "Net-(OC3-Pad1)") (class "Default")
      (node (ref "OC3") (pin "1") (pinfunction "1_1") (pintype "passive"))
      (node (ref "R7") (pin "1") (pinfunction "1_1") (pintype "passive"))
    )
    (net (code "54") (name "Net-(OC4-Pad1)") (class "Default")
      (node (ref "OC4") (pin "1") (pinfunction "1_1") (pintype "passive"))
      (node (ref "R6") (pin "1") (pinfunction "1_1") (pintype "passive"))
    )
    (net (code "55") (name "Net-(OC5-Pad1)") (class "Default")
      (node (ref "OC5") (pin "1") (pinfunction "1_1") (pintype "passive"))
      (node (ref "R13") (pin "1") (pinfunction "1_1") (pintype "passive"))
    )
    (net (code "56") (name "Net-(P5-Pad2)") (class "Default")
      (node (ref "P5") (pin "2") (pinfunction "2_2") (pintype "passive"))
      (node (ref "R14") (pin "2") (pinfunction "2_2") (pintype "passive"))
    )
    (net (code "57") (name "Net-(P5-Pad3)") (class "Default")
      (node (ref "P5") (pin "3") (pinfunction "3_3") (pintype "passive"))
      (node (ref "R15") (pin "2") (pinfunction "2_2") (pintype "passive"))
    )
    (net (code "58") (name "Net-(U4-C1+)") (class "Default")
      (node (ref "C13") (pin "1") (pinfunction "1_1") (pintype "passive"))
      (node (ref "U4") (pin "1") (pinfunction "C1+_1") (pintype "passive"))
    )
    (net (code "59") (name "Net-(U4-C1-)") (class "Default")
      (node (ref "C13") (pin "2") (pinfunction "2_2") (pintype "passive"))
      (node (ref "U4") (pin "3") (pinfunction "C1-_3") (pintype "passive"))
    )
    (net (code "60") (name "Net-(U4-C2+)") (class "Default")
      (node (ref "C19") (pin "1") (pinfunction "1_1") (pintype "passive"))
      (node (ref "U4") (pin "4") (pinfunction "C2+_4") (pintype "passive"))
    )
    (net (code "61") (name "Net-(U4-C2-)") (class "Default")
      (node (ref "C19") (pin "2") (pinfunction "2_2") (pintype "passive"))
      (node (ref "U4") (pin "5") (pinfunction "C2-_5") (pintype "passive"))
    )
    (net (code "62") (name "Net-(U4-V+)") (class "Default")
      (node (ref "C12") (pin "1") (pinfunction "1_1") (pintype "passive"))
      (node (ref "U4") (pin "2") (pinfunction "V+_2") (pintype "power_in"))
    )
    (net (code "63") (name "Net-(U4-V-)") (class "Default")
      (node (ref "C20") (pin "2") (pinfunction "2_2") (pintype "passive"))
      (node (ref "U4") (pin "6") (pinfunction "V-_6") (pintype "power_in"))
    )
    (net (code "64") (name "unconnected-(U1-PC3{slash}TIM1_CH3-Pad20)") (class "Default")
      (node (ref "U1") (pin "20") (pinfunction "PC3/TIM1_CH3_20") (pintype "bidirectional+no_connect"))
    )
    (net (code "65") (name "unconnected-(U4-R2IN-Pad8)") (class "Default")
      (node (ref "U4") (pin "8") (pinfunction "R2IN_8") (pintype "input+no_connect"))
    )
    (net (code "66") (name "unconnected-(U4-R2OUT-Pad9)") (class "Default")
      (node (ref "U4") (pin "9") (pinfunction "R2OUT_9") (pintype "output+no_connect"))
    )
    (net (code "67") (name "unconnected-(U4-T2IN-Pad10)") (class "Default")
      (node (ref "U4") (pin "10") (pinfunction "T2IN_10") (pintype "input+no_connect"))
    )
    (net (code "68") (name "unconnected-(U4-T2OUT-Pad7)") (class "Default")
      (node (ref "U4") (pin "7") (pinfunction "T2OUT_7") (pintype "output+no_connect"))
    )
  )
)
